# PAGE1.net
KiCad netlist of a schematic drawn in Altium Designer
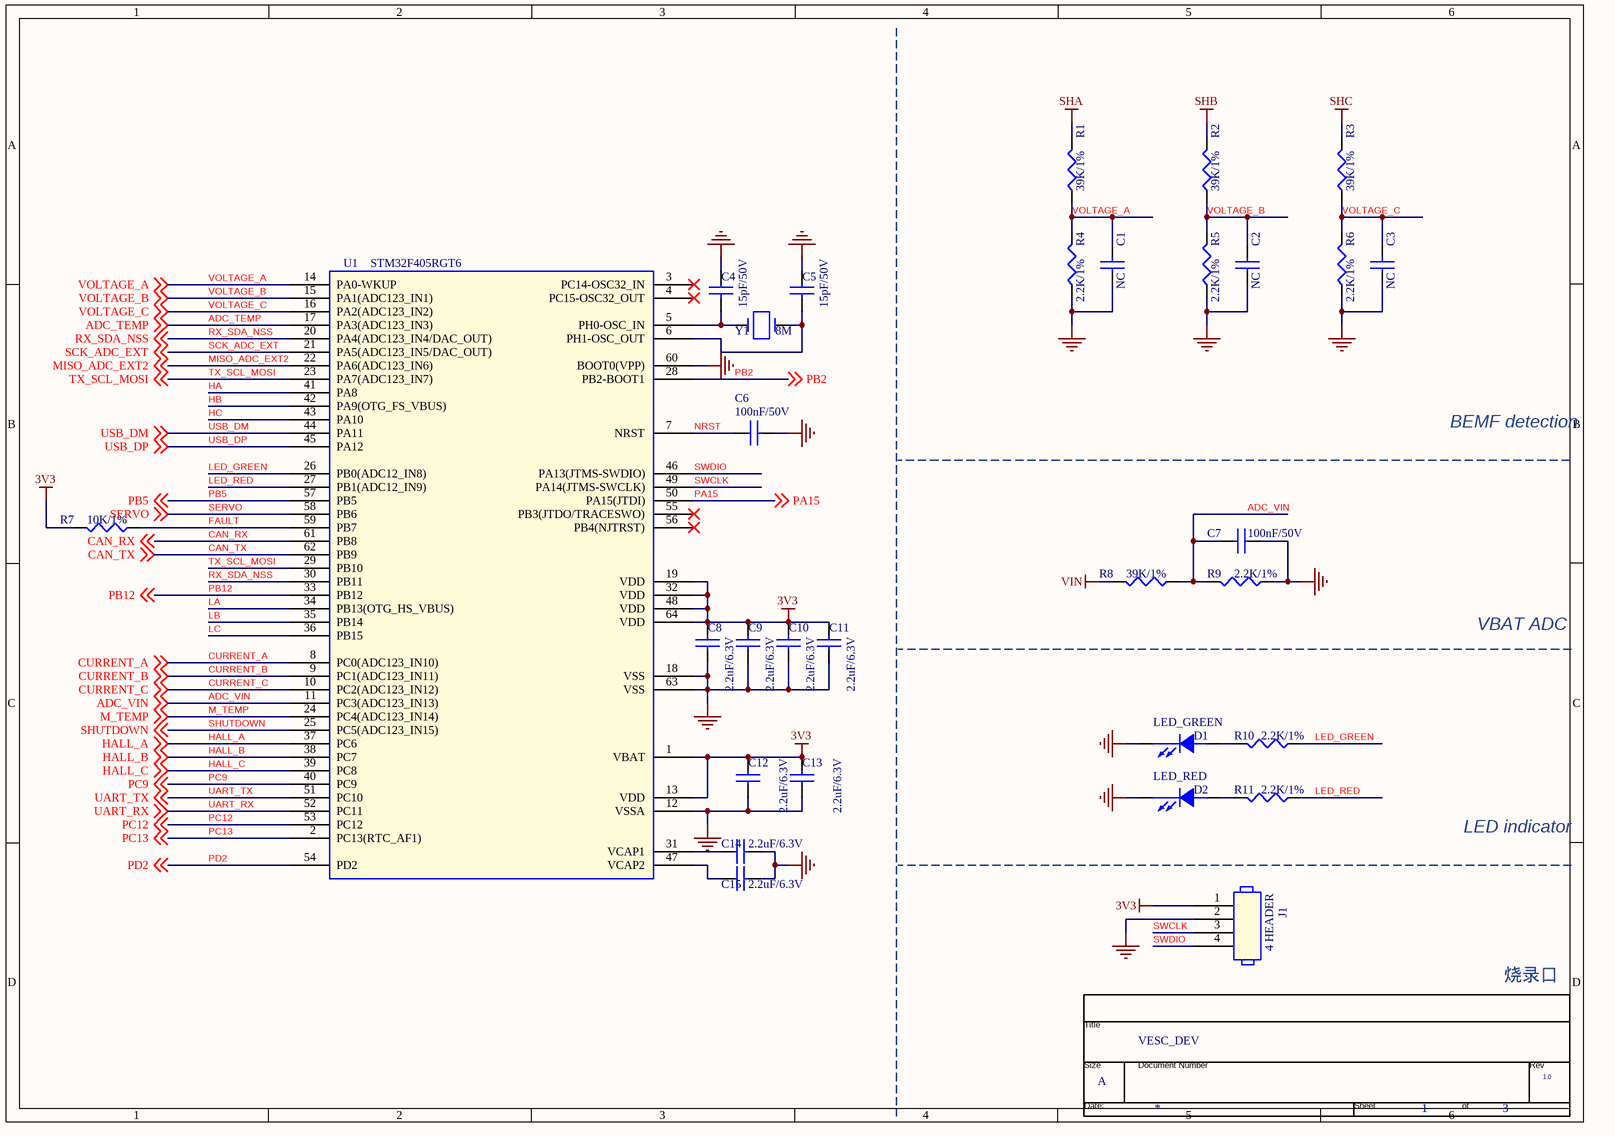
[diagram p0: PAGE1.SchDoc]

(export (version "E")
  (design (tool "Eeschema 10.0.6"))
  (components
    (comp (ref "C1") (value "NC") (footprint "C0402") (libsource (lib "*") (part "CAP NP")))
    (comp (ref "C2") (value "NC") (footprint "C0402") (libsource (lib "*") (part "CAP NP")))
    (comp (ref "C3") (value "NC") (footprint "C0402") (libsource (lib "*") (part "CAP NP")))
    (comp (ref "C4") (value "15pF/50V") (footprint "C0402") (libsource (lib "*") (part "CAP NP")))
    (comp (ref "C5") (value "15pF/50V") (footprint "C0402") (libsource (lib "*") (part "CAP NP")))
    (comp (ref "C6") (value "100nF/50V") (footprint "C0402") (libsource (lib "*") (part "CAP NP")))
    (comp (ref "C7") (value "100nF/50V") (footprint "C0402") (libsource (lib "*") (part "CAP NP")))
    (comp (ref "C8") (value "2.2uF/6.3V") (footprint "C0402") (libsource (lib "*") (part "CAP NP")))
    (comp (ref "C9") (value "2.2uF/6.3V") (footprint "C0402") (libsource (lib "*") (part "CAP NP")))
    (comp (ref "C10") (value "2.2uF/6.3V") (footprint "C0402") (libsource (lib "*") (part "CAP NP")))
    (comp (ref "C11") (value "2.2uF/6.3V") (footprint "C0402") (libsource (lib "*") (part "CAP NP")))
    (comp (ref "C12") (value "2.2uF/6.3V") (footprint "C0402") (libsource (lib "*") (part "CAP NP")))
    (comp (ref "C13") (value "2.2uF/6.3V") (footprint "C0402") (libsource (lib "*") (part "CAP NP")))
    (comp (ref "C14") (value "2.2uF/6.3V") (footprint "C0402") (libsource (lib "*") (part "CAP NP")))
    (comp (ref "C15") (value "2.2uF/6.3V") (footprint "C0402") (libsource (lib "*") (part "CAP NP")))
    (comp (ref "D1") (value "LED_GREEN") (footprint "LED0603") (libsource (lib "*") (part "LED")))
    (comp (ref "D2") (value "LED_RED") (footprint "LED0603") (libsource (lib "*") (part "LED")))
    (comp (ref "J1") (value "4 HEADER") (footprint "ISP-4P-2_54") (libsource (lib "*") (part "4 HEADER")))
    (comp (ref "R1") (value "39K/1%") (footprint "R0402") (libsource (lib "*") (part "RESISTOR")))
    (comp (ref "R2") (value "39K/1%") (footprint "R0402") (libsource (lib "*") (part "RESISTOR")))
    (comp (ref "R3") (value "39K/1%") (footprint "R0402") (libsource (lib "*") (part "RESISTOR")))
    (comp (ref "R4") (value "2.2K/1%") (footprint "R0402") (libsource (lib "*") (part "RESISTOR")))
    (comp (ref "R5") (value "2.2K/1%") (footprint "R0402") (libsource (lib "*") (part "RESISTOR")))
    (comp (ref "R6") (value "2.2K/1%") (footprint "R0402") (libsource (lib "*") (part "RESISTOR")))
    (comp (ref "R7") (value "10K/1%") (footprint "R0402") (libsource (lib "*") (part "RESISTOR")))
    (comp (ref "R8") (value "39K/1%") (footprint "R0402") (libsource (lib "*") (part "RESISTOR")))
    (comp (ref "R9") (value "2.2K/1%") (footprint "R0402") (libsource (lib "*") (part "RESISTOR")))
    (comp (ref "R10") (value "2.2K/1%") (footprint "R0402") (libsource (lib "*") (part "RESISTOR")))
    (comp (ref "R11") (value "2.2K/1%") (footprint "R0402") (libsource (lib "*") (part "RESISTOR")))
    (comp (ref "U1")
      (value "STM32F405RGT6")
      (footprint "LQFP64_10X10_05P")
      (libsource (lib "*") (part "STM32F405RGT6"))
    )
    (comp (ref "Y1") (value "8M") (footprint "SMD5032-2P") (libsource (lib "*") (part "CRYSTAL")))
  )
  (nets
    (net (code "1") (name "/FAULT") (class "Default")
      (node (ref "R7") (pin "1") (pinfunction "1_1") (pintype "passive"))
      (node (ref "U1") (pin "59") (pinfunction "PB7_59") (pintype "passive"))
    )
    (net (code "2") (name "/HA") (class "Default")
      (node (ref "U1") (pin "41") (pinfunction "PA8_41") (pintype "passive"))
    )
    (net (code "3") (name "/HB") (class "Default")
      (node (ref "U1") (pin "42") (pinfunction "PA9(OTG_FS_VBUS)_42") (pintype "passive"))
    )
    (net (code "4") (name "/HC") (class "Default")
      (node (ref "U1") (pin "43") (pinfunction "PA10_43") (pintype "passive"))
    )
    (net (code "5") (name "/LA") (class "Default")
      (node (ref "U1") (pin "34") (pinfunction "PB13(OTG_HS_VBUS)_34") (pintype "passive"))
    )
    (net (code "6") (name "/LB") (class "Default")
      (node (ref "U1") (pin "35") (pinfunction "PB14_35") (pintype "passive"))
    )
    (net (code "7") (name "/LC") (class "Default")
      (node (ref "U1") (pin "36") (pinfunction "PB15_36") (pintype "passive"))
    )
    (net (code "8") (name "/LED_GREEN") (class "Default")
      (node (ref "R10") (pin "1") (pinfunction "1_1") (pintype "passive"))
      (node (ref "U1") (pin "26") (pinfunction "PB0(ADC12_IN8)_26") (pintype "passive"))
    )
    (net (code "9") (name "/LED_RED") (class "Default")
      (node (ref "R11") (pin "1") (pinfunction "1_1") (pintype "passive"))
      (node (ref "U1") (pin "27") (pinfunction "PB1(ADC12_IN9)_27") (pintype "passive"))
    )
    (net (code "10") (name "/NRST") (class "Default")
      (node (ref "C6") (pin "1") (pinfunction "1_1") (pintype "passive"))
      (node (ref "U1") (pin "7") (pinfunction "NRST_7") (pintype "passive"))
    )
    (net (code "11") (name "/SWCLK") (class "Default")
      (node (ref "J1") (pin "3") (pinfunction "3_3") (pintype "passive"))
      (node (ref "U1") (pin "49") (pinfunction "PA14(JTMS-SWCLK)_49") (pintype "passive"))
    )
    (net (code "12") (name "/SWDIO") (class "Default")
      (node (ref "J1") (pin "4") (pinfunction "4_4") (pintype "passive"))
      (node (ref "U1") (pin "46") (pinfunction "PA13(JTMS-SWDIO)_46") (pintype "passive"))
    )
    (net (code "13") (name "3V3") (class "Default")
      (node (ref "C10") (pin "2") (pinfunction "2_2") (pintype "passive"))
      (node (ref "C11") (pin "2") (pinfunction "2_2") (pintype "passive"))
      (node (ref "C12") (pin "2") (pinfunction "2_2") (pintype "passive"))
      (node (ref "C13") (pin "2") (pinfunction "2_2") (pintype "passive"))
      (node (ref "C8") (pin "2") (pinfunction "2_2") (pintype "passive"))
      (node (ref "C9") (pin "2") (pinfunction "2_2") (pintype "passive"))
      (node (ref "J1") (pin "1") (pinfunction "1_1") (pintype "passive"))
      (node (ref "R7") (pin "2") (pinfunction "2_2") (pintype "passive"))
      (node (ref "U1") (pin "1") (pinfunction "VBAT_1") (pintype "power_in"))
      (node (ref "U1") (pin "13") (pinfunction "VDD_13") (pintype "power_in"))
      (node (ref "U1") (pin "19") (pinfunction "VDD_19") (pintype "power_in"))
      (node (ref "U1") (pin "32") (pinfunction "VDD_32") (pintype "power_in"))
      (node (ref "U1") (pin "48") (pinfunction "VDD_48") (pintype "power_in"))
      (node (ref "U1") (pin "64") (pinfunction "VDD_64") (pintype "power_in"))
    )
    (net (code "14") (name "ADC_TEMP") (class "Default")
      (node (ref "U1") (pin "17") (pinfunction "PA3(ADC123_IN3)_17") (pintype "passive"))
    )
    (net (code "15") (name "ADC_VIN") (class "Default")
      (node (ref "C7") (pin "2") (pinfunction "2_2") (pintype "passive"))
      (node (ref "R8") (pin "1") (pinfunction "1_1") (pintype "passive"))
      (node (ref "R9") (pin "2") (pinfunction "2_2") (pintype "passive"))
      (node (ref "U1") (pin "11") (pinfunction "PC3(ADC123_IN13)_11") (pintype "passive"))
    )
    (net (code "16") (name "CAN_RX") (class "Default")
      (node (ref "U1") (pin "61") (pinfunction "PB8_61") (pintype "passive"))
    )
    (net (code "17") (name "CAN_TX") (class "Default")
      (node (ref "U1") (pin "62") (pinfunction "PB9_62") (pintype "passive"))
    )
    (net (code "18") (name "CURRENT_A") (class "Default")
      (node (ref "U1") (pin "8") (pinfunction "PC0(ADC123_IN10)_8") (pintype "passive"))
    )
    (net (code "19") (name "CURRENT_B") (class "Default")
      (node (ref "U1") (pin "9") (pinfunction "PC1(ADC123_IN11)_9") (pintype "passive"))
    )
    (net (code "20") (name "CURRENT_C") (class "Default")
      (node (ref "U1") (pin "10") (pinfunction "PC2(ADC123_IN12)_10") (pintype "passive"))
    )
    (net (code "21") (name "GND") (class "Default")
      (node (ref "C1") (pin "1") (pinfunction "1_1") (pintype "passive"))
      (node (ref "C10") (pin "1") (pinfunction "1_1") (pintype "passive"))
      (node (ref "C11") (pin "1") (pinfunction "1_1") (pintype "passive"))
      (node (ref "C12") (pin "1") (pinfunction "1_1") (pintype "passive"))
      (node (ref "C13") (pin "1") (pinfunction "1_1") (pintype "passive"))
      (node (ref "C14") (pin "2") (pinfunction "2_2") (pintype "passive"))
      (node (ref "C15") (pin "2") (pinfunction "2_2") (pintype "passive"))
      (node (ref "C2") (pin "1") (pinfunction "1_1") (pintype "passive"))
      (node (ref "C3") (pin "1") (pinfunction "1_1") (pintype "passive"))
      (node (ref "C4") (pin "1") (pinfunction "1_1") (pintype "passive"))
      (node (ref "C5") (pin "1") (pinfunction "1_1") (pintype "passive"))
      (node (ref "C6") (pin "2") (pinfunction "2_2") (pintype "passive"))
      (node (ref "C7") (pin "1") (pinfunction "1_1") (pintype "passive"))
      (node (ref "C8") (pin "1") (pinfunction "1_1") (pintype "passive"))
      (node (ref "C9") (pin "1") (pinfunction "1_1") (pintype "passive"))
      (node (ref "D1") (pin "1") (pinfunction "CATHODE_1") (pintype "passive"))
      (node (ref "D2") (pin "1") (pinfunction "CATHODE_1") (pintype "passive"))
      (node (ref "J1") (pin "2") (pinfunction "2_2") (pintype "passive"))
      (node (ref "R4") (pin "1") (pinfunction "1_1") (pintype "passive"))
      (node (ref "R5") (pin "1") (pinfunction "1_1") (pintype "passive"))
      (node (ref "R6") (pin "1") (pinfunction "1_1") (pintype "passive"))
      (node (ref "R9") (pin "1") (pinfunction "1_1") (pintype "passive"))
      (node (ref "U1") (pin "12") (pinfunction "VSSA_12") (pintype "power_in"))
      (node (ref "U1") (pin "18") (pinfunction "VSS_18") (pintype "power_in"))
      (node (ref "U1") (pin "60") (pinfunction "BOOT0(VPP)_60") (pintype "passive"))
      (node (ref "U1") (pin "63") (pinfunction "VSS_63") (pintype "power_in"))
    )
    (net (code "22") (name "HALL_A") (class "Default")
      (node (ref "U1") (pin "37") (pinfunction "PC6_37") (pintype "passive"))
    )
    (net (code "23") (name "HALL_B") (class "Default")
      (node (ref "U1") (pin "38") (pinfunction "PC7_38") (pintype "passive"))
    )
    (net (code "24") (name "HALL_C") (class "Default")
      (node (ref "U1") (pin "39") (pinfunction "PC8_39") (pintype "passive"))
    )
    (net (code "25") (name "MISO_ADC_EXT2") (class "Default")
      (node (ref "U1") (pin "22") (pinfunction "PA6(ADC123_IN6)_22") (pintype "passive"))
    )
    (net (code "26") (name "M_TEMP") (class "Default")
      (node (ref "U1") (pin "24") (pinfunction "PC4(ADC123_IN14)_24") (pintype "passive"))
    )
    (net (code "27") (name "Net-(D1-ANODE)") (class "Default")
      (node (ref "D1") (pin "2") (pinfunction "ANODE_2") (pintype "passive"))
      (node (ref "R10") (pin "2") (pinfunction "2_2") (pintype "passive"))
    )
    (net (code "28") (name "Net-(D2-ANODE)") (class "Default")
      (node (ref "D2") (pin "2") (pinfunction "ANODE_2") (pintype "passive"))
      (node (ref "R11") (pin "2") (pinfunction "2_2") (pintype "passive"))
    )
    (net (code "29") (name "Net-(U1-PH0-OSC_IN)") (class "Default")
      (node (ref "C4") (pin "2") (pinfunction "2_2") (pintype "passive"))
      (node (ref "U1") (pin "5") (pinfunction "PH0-OSC_IN_5") (pintype "passive"))
      (node (ref "Y1") (pin "2") (pinfunction "2_2") (pintype "passive"))
    )
    (net (code "30") (name "Net-(U1-PH1-OSC_OUT)") (class "Default")
      (node (ref "C5") (pin "2") (pinfunction "2_2") (pintype "passive"))
      (node (ref "U1") (pin "6") (pinfunction "PH1-OSC_OUT_6") (pintype "passive"))
      (node (ref "Y1") (pin "1") (pinfunction "1_1") (pintype "passive"))
    )
    (net (code "31") (name "Net-(U1-VCAP1)") (class "Default")
      (node (ref "C14") (pin "1") (pinfunction "1_1") (pintype "passive"))
      (node (ref "U1") (pin "31") (pinfunction "VCAP1_31") (pintype "passive"))
    )
    (net (code "32") (name "Net-(U1-VCAP2)") (class "Default")
      (node (ref "C15") (pin "1") (pinfunction "1_1") (pintype "passive"))
      (node (ref "U1") (pin "47") (pinfunction "VCAP2_47") (pintype "passive"))
    )
    (net (code "33") (name "PA15") (class "Default")
      (node (ref "U1") (pin "50") (pinfunction "PA15(JTDI)_50") (pintype "passive"))
    )
    (net (code "34") (name "PB2") (class "Default")
      (node (ref "U1") (pin "28") (pinfunction "PB2-BOOT1_28") (pintype "passive"))
    )
    (net (code "35") (name "PB5") (class "Default")
      (node (ref "U1") (pin "57") (pinfunction "PB5_57") (pintype "passive"))
    )
    (net (code "36") (name "PB12") (class "Default")
      (node (ref "U1") (pin "33") (pinfunction "PB12_33") (pintype "passive"))
    )
    (net (code "37") (name "PC9") (class "Default")
      (node (ref "U1") (pin "40") (pinfunction "PC9_40") (pintype "passive"))
    )
    (net (code "38") (name "PC12") (class "Default")
      (node (ref "U1") (pin "53") (pinfunction "PC12_53") (pintype "passive"))
    )
    (net (code "39") (name "PC13") (class "Default")
      (node (ref "U1") (pin "2") (pinfunction "PC13(RTC_AF1)_2") (pintype "passive"))
    )
    (net (code "40") (name "PD2") (class "Default")
      (node (ref "U1") (pin "54") (pinfunction "PD2_54") (pintype "passive"))
    )
    (net (code "41") (name "RX_SDA_NSS") (class "Default")
      (node (ref "U1") (pin "20") (pinfunction "PA4(ADC123_IN4/DAC_OUT)_20") (pintype "passive"))
      (node (ref "U1") (pin "30") (pinfunction "PB11_30") (pintype "passive"))
    )
    (net (code "42") (name "SCK_ADC_EXT") (class "Default")
      (node (ref "U1") (pin "21") (pinfunction "PA5(ADC123_IN5/DAC_OUT)_21") (pintype "passive"))
    )
    (net (code "43") (name "SERVO") (class "Default")
      (node (ref "U1") (pin "58") (pinfunction "PB6_58") (pintype "passive"))
    )
    (net (code "44") (name "SHA") (class "Default")
      (node (ref "R1") (pin "2") (pinfunction "2_2") (pintype "passive"))
    )
    (net (code "45") (name "SHB") (class "Default")
      (node (ref "R2") (pin "2") (pinfunction "2_2") (pintype "passive"))
    )
    (net (code "46") (name "SHC") (class "Default")
      (node (ref "R3") (pin "2") (pinfunction "2_2") (pintype "passive"))
    )
    (net (code "47") (name "SHUTDOWN") (class "Default")
      (node (ref "U1") (pin "25") (pinfunction "PC5(ADC123_IN15)_25") (pintype "passive"))
    )
    (net (code "48") (name "TX_SCL_MOSI") (class "Default")
      (node (ref "U1") (pin "23") (pinfunction "PA7(ADC123_IN7)_23") (pintype "passive"))
      (node (ref "U1") (pin "29") (pinfunction "PB10_29") (pintype "passive"))
    )
    (net (code "49") (name "UART_RX") (class "Default")
      (node (ref "U1") (pin "52") (pinfunction "PC11_52") (pintype "passive"))
    )
    (net (code "50") (name "UART_TX") (class "Default")
      (node (ref "U1") (pin "51") (pinfunction "PC10_51") (pintype "passive"))
    )
    (net (code "51") (name "USB_DM") (class "Default")
      (node (ref "U1") (pin "44") (pinfunction "PA11_44") (pintype "passive"))
    )
    (net (code "52") (name "USB_DP") (class "Default")
      (node (ref "U1") (pin "45") (pinfunction "PA12_45") (pintype "passive"))
    )
    (net (code "53") (name "VIN") (class "Default")
      (node (ref "R8") (pin "2") (pinfunction "2_2") (pintype "passive"))
    )
    (net (code "54") (name "VOLTAGE_A") (class "Default")
      (node (ref "C1") (pin "2") (pinfunction "2_2") (pintype "passive"))
      (node (ref "R1") (pin "1") (pinfunction "1_1") (pintype "passive"))
      (node (ref "R4") (pin "2") (pinfunction "2_2") (pintype "passive"))
      (node (ref "U1") (pin "14") (pinfunction "PA0-WKUP_14") (pintype "passive"))
    )
    (net (code "55") (name "VOLTAGE_B") (class "Default")
      (node (ref "C2") (pin "2") (pinfunction "2_2") (pintype "passive"))
      (node (ref "R2") (pin "1") (pinfunction "1_1") (pintype "passive"))
      (node (ref "R5") (pin "2") (pinfunction "2_2") (pintype "passive"))
      (node (ref "U1") (pin "15") (pinfunction "PA1(ADC123_IN1)_15") (pintype "passive"))
    )
    (net (code "56") (name "VOLTAGE_C") (class "Default")
      (node (ref "C3") (pin "2") (pinfunction "2_2") (pintype "passive"))
      (node (ref "R3") (pin "1") (pinfunction "1_1") (pintype "passive"))
      (node (ref "R6") (pin "2") (pinfunction "2_2") (pintype "passive"))
      (node (ref "U1") (pin "16") (pinfunction "PA2(ADC123_IN2)_16") (pintype "passive"))
    )
    (net (code "57") (name "unconnected-(U1-PB3(JTDO{slash}TRACESWO)-Pad55)") (class "Default")
      (node (ref "U1") (pin "55") (pinfunction "PB3(JTDO/TRACESWO)_55") (pintype "passive+no_connect"))
    )
    (net (code "58") (name "unconnected-(U1-PB4(NJTRST)-Pad56)") (class "Default")
      (node (ref "U1") (pin "56") (pinfunction "PB4(NJTRST)_56") (pintype "passive+no_connect"))
    )
    (net (code "59") (name "unconnected-(U1-PC14-OSC32_IN-Pad3)") (class "Default")
      (node (ref "U1") (pin "3") (pinfunction "PC14-OSC32_IN_3") (pintype "passive+no_connect"))
    )
    (net (code "60") (name "unconnected-(U1-PC15-OSC32_OUT-Pad4)") (class "Default")
      (node (ref "U1") (pin "4") (pinfunction "PC15-OSC32_OUT_4") (pintype "passive+no_connect"))
    )
  )
)
